# APRS-ESP32_SA8x8_Rev_A.net
KiCad netlist of a schematic drawn in EAGLE
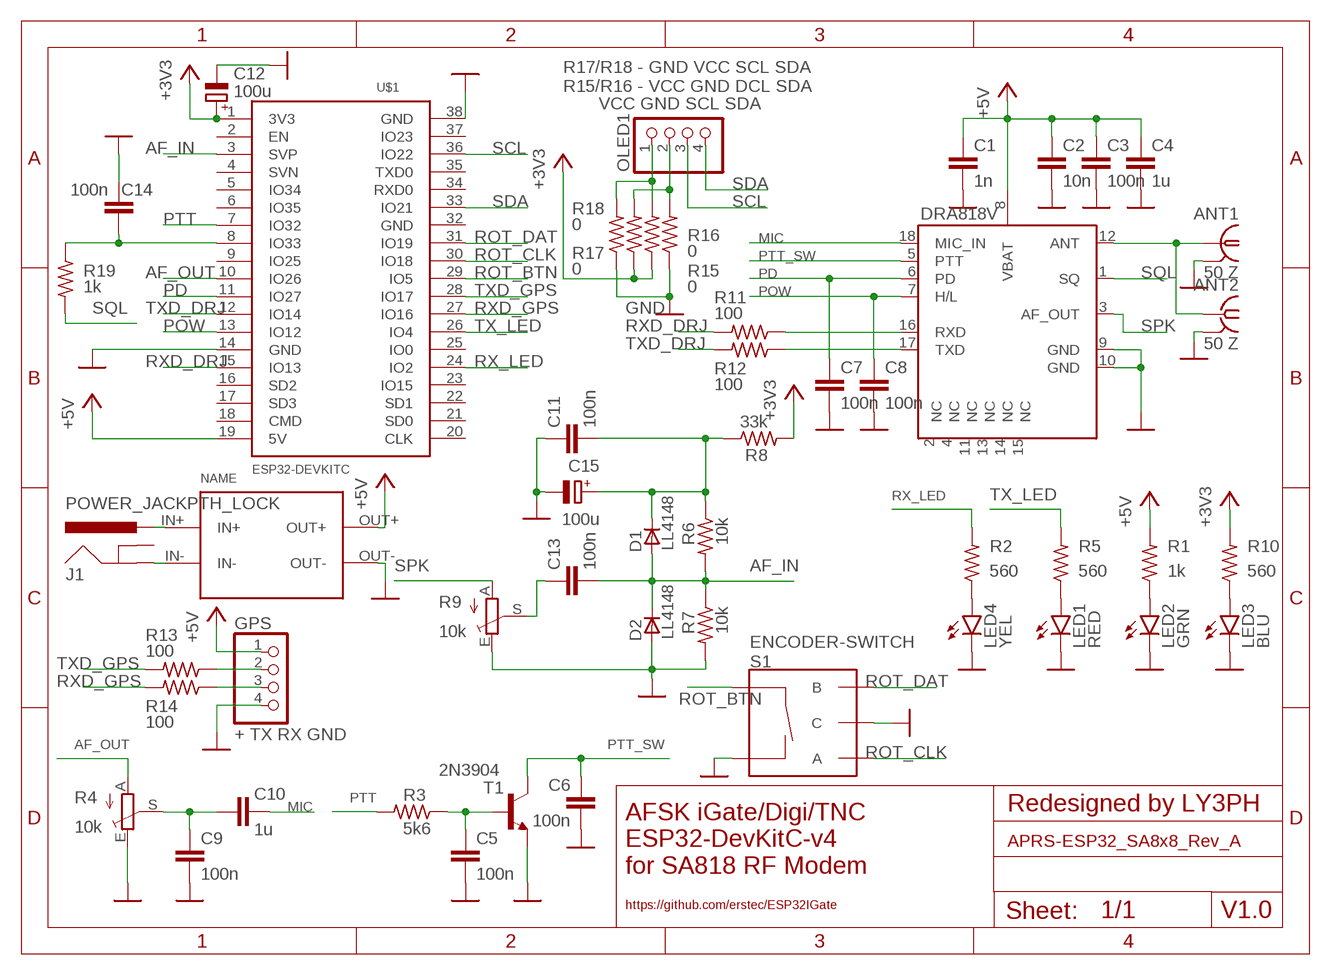
[diagram p0: schematic, sheet 1]

(export (version "E")
  (design (tool "Eeschema 10.0.6"))
  (components
    (comp (ref "ANT1")
      (value "50 Z")
      (footprint "eagle-import:LTI-SASF54GT")
      (libsource (lib "eagle-import") (part "LTI-SASF54GT"))
    )
    (comp (ref "ANT2")
      (value "50 Z")
      (footprint "eagle-import:J502-ND-142-0701-801_806")
      (fields (field (name "MF") "JOHNSON COMPONENTS") (field (name "MPN") "142-0701-801"))
      (libsource (lib "eagle-import") (part "SMA-142-0701-801/806"))
    )
    (comp (ref "C1")
      (value "1n")
      (footprint "eagle-import:C0805")
      (libsource (lib "eagle-import") (part "C-EUC0805"))
    )
    (comp (ref "C2")
      (value "10n")
      (footprint "eagle-import:C0805")
      (libsource (lib "eagle-import") (part "C-EUC0805"))
    )
    (comp (ref "C3")
      (value "100n")
      (footprint "eagle-import:C0805")
      (libsource (lib "eagle-import") (part "C-EUC0805"))
    )
    (comp (ref "C4")
      (value "1u")
      (footprint "eagle-import:C0805")
      (libsource (lib "eagle-import") (part "C-EUC0805"))
    )
    (comp (ref "C5")
      (value "100n")
      (footprint "eagle-import:C0805")
      (libsource (lib "eagle-import") (part "C-EUC0805"))
    )
    (comp (ref "C6")
      (value "100n")
      (footprint "eagle-import:C0805")
      (libsource (lib "eagle-import") (part "C-EUC0805"))
    )
    (comp (ref "C7")
      (value "100n")
      (footprint "eagle-import:C0805")
      (libsource (lib "eagle-import") (part "C-EUC0805"))
    )
    (comp (ref "C8")
      (value "100n")
      (footprint "eagle-import:C0805")
      (libsource (lib "eagle-import") (part "C-EUC0805"))
    )
    (comp (ref "C9")
      (value "100n")
      (footprint "eagle-import:C0805")
      (libsource (lib "eagle-import") (part "C-EUC0805"))
    )
    (comp (ref "C10")
      (value "1u")
      (footprint "eagle-import:C0805")
      (libsource (lib "eagle-import") (part "C-EUC0805"))
    )
    (comp (ref "C11")
      (value "100n")
      (footprint "eagle-import:C0805")
      (libsource (lib "eagle-import") (part "C-EUC0805"))
    )
    (comp (ref "C12")
      (value "100u")
      (footprint "eagle-import:SMC_D")
      (libsource (lib "eagle-import") (part "CPOL-EUSMCD"))
    )
    (comp (ref "C13")
      (value "100n")
      (footprint "eagle-import:C0805")
      (libsource (lib "eagle-import") (part "C-EUC0805"))
    )
    (comp (ref "C14")
      (value "100n")
      (footprint "eagle-import:C0805")
      (libsource (lib "eagle-import") (part "C-EUC0805"))
    )
    (comp (ref "C15")
      (value "100u")
      (footprint "eagle-import:SMC_D")
      (libsource (lib "eagle-import") (part "CPOL-EUSMCD"))
    )
    (comp (ref "D1")
      (value "LL4148")
      (footprint "eagle-import:SOD80_DO213AA_MINIMELF")
      (libsource (lib "eagle-import") (part "LL4148"))
    )
    (comp (ref "D2")
      (value "LL4148")
      (footprint "eagle-import:SOD80_DO213AA_MINIMELF")
      (libsource (lib "eagle-import") (part "LL4148"))
    )
    (comp (ref "DRA818V")
      (value "DRA818A")
      (footprint "eagle-import:DRA818A")
      (libsource (lib "eagle-import") (part "DRA818A"))
    )
    (comp (ref "GPS")
      (value "+ TX RX GND")
      (footprint "eagle-import:1X04")
      (libsource (lib "eagle-import") (part "PINHD-1X4"))
    )
    (comp (ref "J1")
      (value "POWER_JACKPTH_LOCK")
      (footprint "eagle-import:POWER_JACK_PTH_LOCK")
      (libsource (lib "eagle-import") (part "POWER_JACKPTH_LOCK"))
    )
    (comp (ref "LED1")
      (value "RED")
      (footprint "eagle-import:CHIP-LED0805")
      (libsource (lib "eagle-import") (part "LEDCHIP-LED0805"))
    )
    (comp (ref "LED2")
      (value "GRN")
      (footprint "eagle-import:CHIP-LED0805")
      (libsource (lib "eagle-import") (part "LEDCHIP-LED0805"))
    )
    (comp (ref "LED3")
      (value "BLU")
      (footprint "eagle-import:CHIP-LED0805")
      (libsource (lib "eagle-import") (part "LEDCHIP-LED0805"))
    )
    (comp (ref "LED4")
      (value "YEL")
      (footprint "eagle-import:CHIP-LED0805")
      (libsource (lib "eagle-import") (part "LEDCHIP-LED0805"))
    )
    (comp (ref "OLED1")
      (value "VCC GND SCL SDA")
      (footprint "eagle-import:1X04")
      (libsource (lib "eagle-import") (part "PINHD-1X4"))
    )
    (comp (ref "R1")
      (value "1k")
      (footprint "eagle-import:R0805")
      (libsource (lib "eagle-import") (part "R-US_R0805"))
    )
    (comp (ref "R2")
      (value "560")
      (footprint "eagle-import:R0805")
      (libsource (lib "eagle-import") (part "R-US_R0805"))
    )
    (comp (ref "R3")
      (value "5k6")
      (footprint "eagle-import:R0805")
      (libsource (lib "eagle-import") (part "R-US_R0805"))
    )
    (comp (ref "R4")
      (value "10k")
      (footprint "eagle-import:CA6H")
      (libsource (lib "eagle-import") (part "TRIM_EU-CA6H"))
    )
    (comp (ref "R5")
      (value "560")
      (footprint "eagle-import:R0805")
      (libsource (lib "eagle-import") (part "R-US_R0805"))
    )
    (comp (ref "R6")
      (value "10k")
      (footprint "eagle-import:R0805")
      (libsource (lib "eagle-import") (part "R-US_R0805"))
    )
    (comp (ref "R7")
      (value "10k")
      (footprint "eagle-import:R0805")
      (libsource (lib "eagle-import") (part "R-US_R0805"))
    )
    (comp (ref "R8")
      (value "33k")
      (footprint "eagle-import:R0805")
      (libsource (lib "eagle-import") (part "R-US_R0805"))
    )
    (comp (ref "R9")
      (value "10k")
      (footprint "eagle-import:CA6H")
      (libsource (lib "eagle-import") (part "TRIM_EU-CA6H"))
    )
    (comp (ref "R10")
      (value "560")
      (footprint "eagle-import:R0805")
      (libsource (lib "eagle-import") (part "R-US_R0805"))
    )
    (comp (ref "R11")
      (value "100")
      (footprint "eagle-import:R0805")
      (libsource (lib "eagle-import") (part "R-US_R0805"))
    )
    (comp (ref "R12")
      (value "100")
      (footprint "eagle-import:R0805")
      (libsource (lib "eagle-import") (part "R-US_R0805"))
    )
    (comp (ref "R13")
      (value "100")
      (footprint "eagle-import:R0805")
      (libsource (lib "eagle-import") (part "R-US_R0805"))
    )
    (comp (ref "R14")
      (value "100")
      (footprint "eagle-import:R0805")
      (libsource (lib "eagle-import") (part "R-US_R0805"))
    )
    (comp (ref "R15")
      (value "0")
      (footprint "eagle-import:R0805")
      (libsource (lib "eagle-import") (part "R-US_R0805"))
    )
    (comp (ref "R16")
      (value "0")
      (footprint "eagle-import:R0805")
      (libsource (lib "eagle-import") (part "R-US_R0805"))
    )
    (comp (ref "R17")
      (value "0")
      (footprint "eagle-import:R0805")
      (libsource (lib "eagle-import") (part "R-US_R0805"))
    )
    (comp (ref "R18")
      (value "0")
      (footprint "eagle-import:R0805")
      (libsource (lib "eagle-import") (part "R-US_R0805"))
    )
    (comp (ref "R19")
      (value "1k")
      (footprint "eagle-import:R0805")
      (libsource (lib "eagle-import") (part "R-US_R0805"))
    )
    (comp (ref "S1")
      (value "ENCODER-SWITCH")
      (footprint "eagle-import:ROTARY_ENC_PLAIN")
      (libsource (lib "eagle-import") (part "ENCODER-SWITCH"))
    )
    (comp (ref "T1")
      (value "2N3904")
      (footprint "eagle-import:SOT23-BEC")
      (libsource (lib "eagle-import") (part "-NPN-SOT23-BECMMBT3904LT1"))
    )
    (comp (ref "U$1")
      (value "ESP32DEVKITC")
      (footprint "eagle-import:ESP32-DEVKITC")
      (libsource (lib "eagle-import") (part "ESP32DEVKITC"))
    )
    (comp (ref "U$2")
      (value "CP8-ADJ")
      (footprint "eagle-import:CP8-ADJ")
      (libsource (lib "eagle-import") (part "CP8-ADJ"))
    )
  )
  (nets
    (net (code "1") (name "+3V3") (class "Default")
      (node (ref "C12") (pin "+") (pinfunction "+_+") (pintype "passive"))
      (node (ref "R10") (pin "2") (pinfunction "2_2") (pintype "passive"))
      (node (ref "R15") (pin "1") (pinfunction "1_1") (pintype "passive"))
      (node (ref "R17") (pin "1") (pinfunction "1_1") (pintype "passive"))
      (node (ref "R8") (pin "2") (pinfunction "2_2") (pintype "passive"))
      (node (ref "U$1") (pin "1") (pinfunction "3V3_1") (pintype "bidirectional"))
    )
    (net (code "2") (name "+5V") (class "Default")
      (node (ref "C1") (pin "1") (pinfunction "1_1") (pintype "passive"))
      (node (ref "C2") (pin "1") (pinfunction "1_1") (pintype "passive"))
      (node (ref "C3") (pin "1") (pinfunction "1_1") (pintype "passive"))
      (node (ref "C4") (pin "1") (pinfunction "1_1") (pintype "passive"))
      (node (ref "DRA818V") (pin "8") (pinfunction "VBAT_8") (pintype "bidirectional"))
      (node (ref "GPS") (pin "1") (pinfunction "1_1") (pintype "passive"))
      (node (ref "R1") (pin "2") (pinfunction "2_2") (pintype "passive"))
      (node (ref "U$1") (pin "19") (pinfunction "5V_19") (pintype "bidirectional"))
      (node (ref "U$2") (pin "OUT+") (pinfunction "OUT+_OUT+") (pintype "passive"))
    )
    (net (code "3") (name "/AF_IN") (class "Default")
      (node (ref "C13") (pin "2") (pinfunction "2_2") (pintype "passive"))
      (node (ref "D1") (pin "A") (pinfunction "A_A") (pintype "passive"))
      (node (ref "D2") (pin "C") (pinfunction "C_C") (pintype "passive"))
      (node (ref "R6") (pin "2") (pinfunction "2_2") (pintype "passive"))
      (node (ref "R7") (pin "1") (pinfunction "1_1") (pintype "passive"))
      (node (ref "U$1") (pin "3") (pinfunction "SVP_3") (pintype "bidirectional"))
    )
    (net (code "4") (name "/AF_OUT") (class "Default")
      (node (ref "R4") (pin "A") (pinfunction "A_A") (pintype "passive"))
      (node (ref "U$1") (pin "10") (pinfunction "IO26_10") (pintype "bidirectional"))
    )
    (net (code "5") (name "/MIC") (class "Default")
      (node (ref "C10") (pin "2") (pinfunction "2_2") (pintype "passive"))
      (node (ref "DRA818V") (pin "18") (pinfunction "MIC_IN_18") (pintype "bidirectional"))
    )
    (net (code "6") (name "/PD") (class "Default")
      (node (ref "C7") (pin "1") (pinfunction "1_1") (pintype "passive"))
      (node (ref "DRA818V") (pin "6") (pinfunction "PD_6") (pintype "bidirectional"))
      (node (ref "U$1") (pin "11") (pinfunction "IO27_11") (pintype "bidirectional"))
    )
    (net (code "7") (name "/POW") (class "Default")
      (node (ref "C8") (pin "1") (pinfunction "1_1") (pintype "passive"))
      (node (ref "DRA818V") (pin "7") (pinfunction "H/L_7") (pintype "bidirectional"))
      (node (ref "U$1") (pin "13") (pinfunction "IO12_13") (pintype "bidirectional"))
    )
    (net (code "8") (name "/PTT") (class "Default")
      (node (ref "R3") (pin "2") (pinfunction "2_2") (pintype "passive"))
      (node (ref "U$1") (pin "7") (pinfunction "IO32_7") (pintype "bidirectional"))
    )
    (net (code "9") (name "/PTT_SW") (class "Default")
      (node (ref "C6") (pin "1") (pinfunction "1_1") (pintype "passive"))
      (node (ref "DRA818V") (pin "5") (pinfunction "PTT_5") (pintype "bidirectional"))
      (node (ref "T1") (pin "C") (pinfunction "C_C") (pintype "passive"))
    )
    (net (code "10") (name "/ROT_BTN") (class "Default")
      (node (ref "S1") (pin "SW+") (pinfunction "SW+_SW+") (pintype "bidirectional"))
      (node (ref "U$1") (pin "29") (pinfunction "IO5_29") (pintype "bidirectional"))
    )
    (net (code "11") (name "/ROT_CLK") (class "Default")
      (node (ref "S1") (pin "A") (pinfunction "A_A") (pintype "bidirectional"))
      (node (ref "U$1") (pin "30") (pinfunction "IO18_30") (pintype "bidirectional"))
    )
    (net (code "12") (name "/ROT_DAT") (class "Default")
      (node (ref "S1") (pin "B") (pinfunction "B_B") (pintype "bidirectional"))
      (node (ref "U$1") (pin "31") (pinfunction "IO19_31") (pintype "bidirectional"))
    )
    (net (code "13") (name "/RXD_DRJ") (class "Default")
      (node (ref "R11") (pin "2") (pinfunction "2_2") (pintype "passive"))
      (node (ref "U$1") (pin "15") (pinfunction "IO13_15") (pintype "bidirectional"))
    )
    (net (code "14") (name "/RXD_GPS") (class "Default")
      (node (ref "R14") (pin "2") (pinfunction "2_2") (pintype "passive"))
      (node (ref "U$1") (pin "27") (pinfunction "IO16_27") (pintype "bidirectional"))
    )
    (net (code "15") (name "/RX_LED") (class "Default")
      (node (ref "R2") (pin "2") (pinfunction "2_2") (pintype "passive"))
      (node (ref "U$1") (pin "24") (pinfunction "IO2_24") (pintype "bidirectional"))
    )
    (net (code "16") (name "/SCL") (class "Default")
      (node (ref "OLED1") (pin "3") (pinfunction "3_3") (pintype "passive"))
      (node (ref "U$1") (pin "36") (pinfunction "IO22_36") (pintype "bidirectional"))
    )
    (net (code "17") (name "/SDA") (class "Default")
      (node (ref "OLED1") (pin "4") (pinfunction "4_4") (pintype "passive"))
      (node (ref "U$1") (pin "33") (pinfunction "IO21_33") (pintype "bidirectional"))
    )
    (net (code "18") (name "/SPK") (class "Default")
      (node (ref "DRA818V") (pin "3") (pinfunction "AF_OUT_3") (pintype "bidirectional"))
      (node (ref "R9") (pin "A") (pinfunction "A_A") (pintype "passive"))
    )
    (net (code "19") (name "/SQL") (class "Default")
      (node (ref "DRA818V") (pin "1") (pinfunction "SQ_1") (pintype "bidirectional"))
      (node (ref "R19") (pin "2") (pinfunction "2_2") (pintype "passive"))
    )
    (net (code "20") (name "/TXD_DRJ") (class "Default")
      (node (ref "R12") (pin "2") (pinfunction "2_2") (pintype "passive"))
      (node (ref "U$1") (pin "12") (pinfunction "IO14_12") (pintype "bidirectional"))
    )
    (net (code "21") (name "/TXD_GPS") (class "Default")
      (node (ref "R13") (pin "2") (pinfunction "2_2") (pintype "passive"))
      (node (ref "U$1") (pin "28") (pinfunction "IO17_28") (pintype "bidirectional"))
    )
    (net (code "22") (name "/TX_LED") (class "Default")
      (node (ref "R5") (pin "2") (pinfunction "2_2") (pintype "passive"))
      (node (ref "U$1") (pin "26") (pinfunction "IO4_26") (pintype "bidirectional"))
    )
    (net (code "23") (name "GND") (class "Default")
      (node (ref "ANT1") (pin "2") (pinfunction "2_2") (pintype "passive"))
      (node (ref "ANT1") (pin "3") (pinfunction "2_3") (pintype "passive"))
      (node (ref "ANT1") (pin "4") (pinfunction "2_4") (pintype "passive"))
      (node (ref "ANT1") (pin "5") (pinfunction "2_5") (pintype "passive"))
      (node (ref "ANT2") (pin "G@1") (pinfunction "2_G@1") (pintype "passive"))
      (node (ref "ANT2") (pin "G@2") (pinfunction "2_G@2") (pintype "passive"))
      (node (ref "ANT2") (pin "G@3") (pinfunction "2_G@3") (pintype "passive"))
      (node (ref "ANT2") (pin "G@4") (pinfunction "2_G@4") (pintype "passive"))
      (node (ref "C1") (pin "2") (pinfunction "2_2") (pintype "passive"))
      (node (ref "C11") (pin "1") (pinfunction "1_1") (pintype "passive"))
      (node (ref "C12") (pin "-") (pinfunction "-_-") (pintype "passive"))
      (node (ref "C14") (pin "2") (pinfunction "2_2") (pintype "passive"))
      (node (ref "C15") (pin "-") (pinfunction "-_-") (pintype "passive"))
      (node (ref "C2") (pin "2") (pinfunction "2_2") (pintype "passive"))
      (node (ref "C3") (pin "2") (pinfunction "2_2") (pintype "passive"))
      (node (ref "C4") (pin "2") (pinfunction "2_2") (pintype "passive"))
      (node (ref "C5") (pin "2") (pinfunction "2_2") (pintype "passive"))
      (node (ref "C6") (pin "2") (pinfunction "2_2") (pintype "passive"))
      (node (ref "C7") (pin "2") (pinfunction "2_2") (pintype "passive"))
      (node (ref "C8") (pin "2") (pinfunction "2_2") (pintype "passive"))
      (node (ref "C9") (pin "2") (pinfunction "2_2") (pintype "passive"))
      (node (ref "D2") (pin "A") (pinfunction "A_A") (pintype "passive"))
      (node (ref "DRA818V") (pin "10") (pinfunction "GND_10") (pintype "bidirectional"))
      (node (ref "DRA818V") (pin "9") (pinfunction "GND_9") (pintype "bidirectional"))
      (node (ref "GPS") (pin "4") (pinfunction "4_4") (pintype "passive"))
      (node (ref "LED1") (pin "C") (pinfunction "C_C") (pintype "passive"))
      (node (ref "LED2") (pin "C") (pinfunction "C_C") (pintype "passive"))
      (node (ref "LED3") (pin "C") (pinfunction "C_C") (pintype "passive"))
      (node (ref "LED4") (pin "C") (pinfunction "C_C") (pintype "passive"))
      (node (ref "R16") (pin "1") (pinfunction "1_1") (pintype "passive"))
      (node (ref "R18") (pin "1") (pinfunction "1_1") (pintype "passive"))
      (node (ref "R4") (pin "E") (pinfunction "E_E") (pintype "passive"))
      (node (ref "R7") (pin "2") (pinfunction "2_2") (pintype "passive"))
      (node (ref "R9") (pin "E") (pinfunction "E_E") (pintype "passive"))
      (node (ref "S1") (pin "C") (pinfunction "C_C") (pintype "bidirectional"))
      (node (ref "S1") (pin "SW-") (pinfunction "SW-_SW-") (pintype "bidirectional"))
      (node (ref "T1") (pin "E") (pinfunction "E_E") (pintype "passive"))
      (node (ref "U$1") (pin "14") (pinfunction "GND_14") (pintype "bidirectional"))
      (node (ref "U$1") (pin "38") (pinfunction "GND_38") (pintype "bidirectional"))
      (node (ref "U$2") (pin "OUT-") (pinfunction "OUT-_OUT-") (pintype "passive"))
    )
    (net (code "24") (name "Net-(C5-Pad1)") (class "Default")
      (node (ref "C5") (pin "1") (pinfunction "1_1") (pintype "passive"))
      (node (ref "R3") (pin "1") (pinfunction "1_1") (pintype "passive"))
      (node (ref "T1") (pin "B") (pinfunction "B_B") (pintype "passive"))
    )
    (net (code "25") (name "Net-(C10-Pad1)") (class "Default")
      (node (ref "C10") (pin "1") (pinfunction "1_1") (pintype "passive"))
      (node (ref "C9") (pin "1") (pinfunction "1_1") (pintype "passive"))
      (node (ref "R4") (pin "S") (pinfunction "S_S") (pintype "passive"))
    )
    (net (code "26") (name "Net-(C11-Pad2)") (class "Default")
      (node (ref "C11") (pin "2") (pinfunction "2_2") (pintype "passive"))
      (node (ref "C15") (pin "+") (pinfunction "+_+") (pintype "passive"))
      (node (ref "D1") (pin "C") (pinfunction "C_C") (pintype "passive"))
      (node (ref "R6") (pin "1") (pinfunction "1_1") (pintype "passive"))
      (node (ref "R8") (pin "1") (pinfunction "1_1") (pintype "passive"))
    )
    (net (code "27") (name "Net-(C13-Pad1)") (class "Default")
      (node (ref "C13") (pin "1") (pinfunction "1_1") (pintype "passive"))
      (node (ref "R9") (pin "S") (pinfunction "S_S") (pintype "passive"))
    )
    (net (code "28") (name "Net-(DRA818V-ANT)") (class "Default")
      (node (ref "ANT1") (pin "1") (pinfunction "1_1") (pintype "passive"))
      (node (ref "ANT2") (pin "1") (pinfunction "1_1") (pintype "passive"))
      (node (ref "DRA818V") (pin "12") (pinfunction "ANT_12") (pintype "bidirectional"))
    )
    (net (code "29") (name "Net-(DRA818V-RXD)") (class "Default")
      (node (ref "DRA818V") (pin "16") (pinfunction "RXD_16") (pintype "bidirectional"))
      (node (ref "R11") (pin "1") (pinfunction "1_1") (pintype "passive"))
    )
    (net (code "30") (name "Net-(DRA818V-TXD)") (class "Default")
      (node (ref "DRA818V") (pin "17") (pinfunction "TXD_17") (pintype "bidirectional"))
      (node (ref "R12") (pin "1") (pinfunction "1_1") (pintype "passive"))
    )
    (net (code "31") (name "Net-(GPS-Pad2)") (class "Default")
      (node (ref "GPS") (pin "2") (pinfunction "2_2") (pintype "passive"))
      (node (ref "R13") (pin "1") (pinfunction "1_1") (pintype "passive"))
    )
    (net (code "32") (name "Net-(GPS-Pad3)") (class "Default")
      (node (ref "GPS") (pin "3") (pinfunction "3_3") (pintype "passive"))
      (node (ref "R14") (pin "1") (pinfunction "1_1") (pintype "passive"))
    )
    (net (code "33") (name "Net-(J1-PadGND)") (class "Default")
      (node (ref "J1") (pin "GND") (pinfunction "GND_GND") (pintype "bidirectional"))
      (node (ref "U$2") (pin "IN-") (pinfunction "IN-_IN-") (pintype "passive"))
    )
    (net (code "34") (name "Net-(J1-PadPWR)") (class "Default")
      (node (ref "J1") (pin "PWR") (pinfunction "PWR_PWR") (pintype "bidirectional"))
      (node (ref "U$2") (pin "IN+") (pinfunction "IN+_IN+") (pintype "passive"))
    )
    (net (code "35") (name "Net-(LED1-PadA)") (class "Default")
      (node (ref "LED1") (pin "A") (pinfunction "A_A") (pintype "passive"))
      (node (ref "R5") (pin "1") (pinfunction "1_1") (pintype "passive"))
    )
    (net (code "36") (name "Net-(LED2-PadA)") (class "Default")
      (node (ref "LED2") (pin "A") (pinfunction "A_A") (pintype "passive"))
      (node (ref "R1") (pin "1") (pinfunction "1_1") (pintype "passive"))
    )
    (net (code "37") (name "Net-(LED3-PadA)") (class "Default")
      (node (ref "LED3") (pin "A") (pinfunction "A_A") (pintype "passive"))
      (node (ref "R10") (pin "1") (pinfunction "1_1") (pintype "passive"))
    )
    (net (code "38") (name "Net-(LED4-PadA)") (class "Default")
      (node (ref "LED4") (pin "A") (pinfunction "A_A") (pintype "passive"))
      (node (ref "R2") (pin "1") (pinfunction "1_1") (pintype "passive"))
    )
    (net (code "39") (name "Net-(OLED1-Pad1)") (class "Default")
      (node (ref "OLED1") (pin "1") (pinfunction "1_1") (pintype "passive"))
      (node (ref "R15") (pin "2") (pinfunction "2_2") (pintype "passive"))
      (node (ref "R18") (pin "2") (pinfunction "2_2") (pintype "passive"))
    )
    (net (code "40") (name "Net-(OLED1-Pad2)") (class "Default")
      (node (ref "OLED1") (pin "2") (pinfunction "2_2") (pintype "passive"))
      (node (ref "R16") (pin "2") (pinfunction "2_2") (pintype "passive"))
      (node (ref "R17") (pin "2") (pinfunction "2_2") (pintype "passive"))
    )
    (net (code "41") (name "Net-(U$1-IO33)") (class "Default")
      (node (ref "C14") (pin "1") (pinfunction "1_1") (pintype "passive"))
      (node (ref "R19") (pin "1") (pinfunction "1_1") (pintype "passive"))
      (node (ref "U$1") (pin "8") (pinfunction "IO33_8") (pintype "bidirectional"))
    )
    (net (code "42") (name "unconnected-(DRA818V-NC-Pad2)") (class "Default")
      (node (ref "DRA818V") (pin "2") (pinfunction "NC_2") (pintype "bidirectional"))
    )
    (net (code "43") (name "unconnected-(DRA818V-NC-Pad4)") (class "Default")
      (node (ref "DRA818V") (pin "4") (pinfunction "NC_4") (pintype "bidirectional"))
    )
    (net (code "44") (name "unconnected-(DRA818V-NC-Pad11)") (class "Default")
      (node (ref "DRA818V") (pin "11") (pinfunction "NC_11") (pintype "bidirectional"))
    )
    (net (code "45") (name "unconnected-(DRA818V-NC-Pad13)") (class "Default")
      (node (ref "DRA818V") (pin "13") (pinfunction "NC_13") (pintype "bidirectional"))
    )
    (net (code "46") (name "unconnected-(DRA818V-NC-Pad14)") (class "Default")
      (node (ref "DRA818V") (pin "14") (pinfunction "NC_14") (pintype "bidirectional"))
    )
    (net (code "47") (name "unconnected-(DRA818V-NC-Pad15)") (class "Default")
      (node (ref "DRA818V") (pin "15") (pinfunction "NC_15") (pintype "bidirectional"))
    )
    (net (code "48") (name "unconnected-(J1-PadGNDBREAK)") (class "Default")
      (node (ref "J1") (pin "GNDBREAK") (pinfunction "GNDBREAK_GNDBREAK") (pintype "bidirectional"))
    )
    (net (code "49") (name "unconnected-(U$1-CLK-Pad20)") (class "Default")
      (node (ref "U$1") (pin "20") (pinfunction "CLK_20") (pintype "bidirectional"))
    )
    (net (code "50") (name "unconnected-(U$1-CMD-Pad18)") (class "Default")
      (node (ref "U$1") (pin "18") (pinfunction "CMD_18") (pintype "bidirectional"))
    )
    (net (code "51") (name "unconnected-(U$1-EN-Pad2)") (class "Default")
      (node (ref "U$1") (pin "2") (pinfunction "EN_2") (pintype "bidirectional"))
    )
    (net (code "52") (name "unconnected-(U$1-GND-Pad32)") (class "Default")
      (node (ref "U$1") (pin "32") (pinfunction "GND_32") (pintype "bidirectional"))
    )
    (net (code "53") (name "unconnected-(U$1-IO0-Pad25)") (class "Default")
      (node (ref "U$1") (pin "25") (pinfunction "IO0_25") (pintype "bidirectional"))
    )
    (net (code "54") (name "unconnected-(U$1-IO15-Pad23)") (class "Default")
      (node (ref "U$1") (pin "23") (pinfunction "IO15_23") (pintype "bidirectional"))
    )
    (net (code "55") (name "unconnected-(U$1-IO23-Pad37)") (class "Default")
      (node (ref "U$1") (pin "37") (pinfunction "IO23_37") (pintype "bidirectional"))
    )
    (net (code "56") (name "unconnected-(U$1-IO25-Pad9)") (class "Default")
      (node (ref "U$1") (pin "9") (pinfunction "IO25_9") (pintype "bidirectional"))
    )
    (net (code "57") (name "unconnected-(U$1-IO34-Pad5)") (class "Default")
      (node (ref "U$1") (pin "5") (pinfunction "IO34_5") (pintype "bidirectional"))
    )
    (net (code "58") (name "unconnected-(U$1-IO35-Pad6)") (class "Default")
      (node (ref "U$1") (pin "6") (pinfunction "IO35_6") (pintype "bidirectional"))
    )
    (net (code "59") (name "unconnected-(U$1-RXD0-Pad34)") (class "Default")
      (node (ref "U$1") (pin "34") (pinfunction "RXD0_34") (pintype "bidirectional"))
    )
    (net (code "60") (name "unconnected-(U$1-SD0-Pad21)") (class "Default")
      (node (ref "U$1") (pin "21") (pinfunction "SD0_21") (pintype "bidirectional"))
    )
    (net (code "61") (name "unconnected-(U$1-SD1-Pad22)") (class "Default")
      (node (ref "U$1") (pin "22") (pinfunction "SD1_22") (pintype "bidirectional"))
    )
    (net (code "62") (name "unconnected-(U$1-SD2-Pad16)") (class "Default")
      (node (ref "U$1") (pin "16") (pinfunction "SD2_16") (pintype "bidirectional"))
    )
    (net (code "63") (name "unconnected-(U$1-SD3-Pad17)") (class "Default")
      (node (ref "U$1") (pin "17") (pinfunction "SD3_17") (pintype "bidirectional"))
    )
    (net (code "64") (name "unconnected-(U$1-SVN-Pad4)") (class "Default")
      (node (ref "U$1") (pin "4") (pinfunction "SVN_4") (pintype "bidirectional"))
    )
    (net (code "65") (name "unconnected-(U$1-TXD0-Pad35)") (class "Default")
      (node (ref "U$1") (pin "35") (pinfunction "TXD0_35") (pintype "bidirectional"))
    )
  )
)
